# PMP9755.net
KiCad netlist of a schematic drawn in Altium Designer
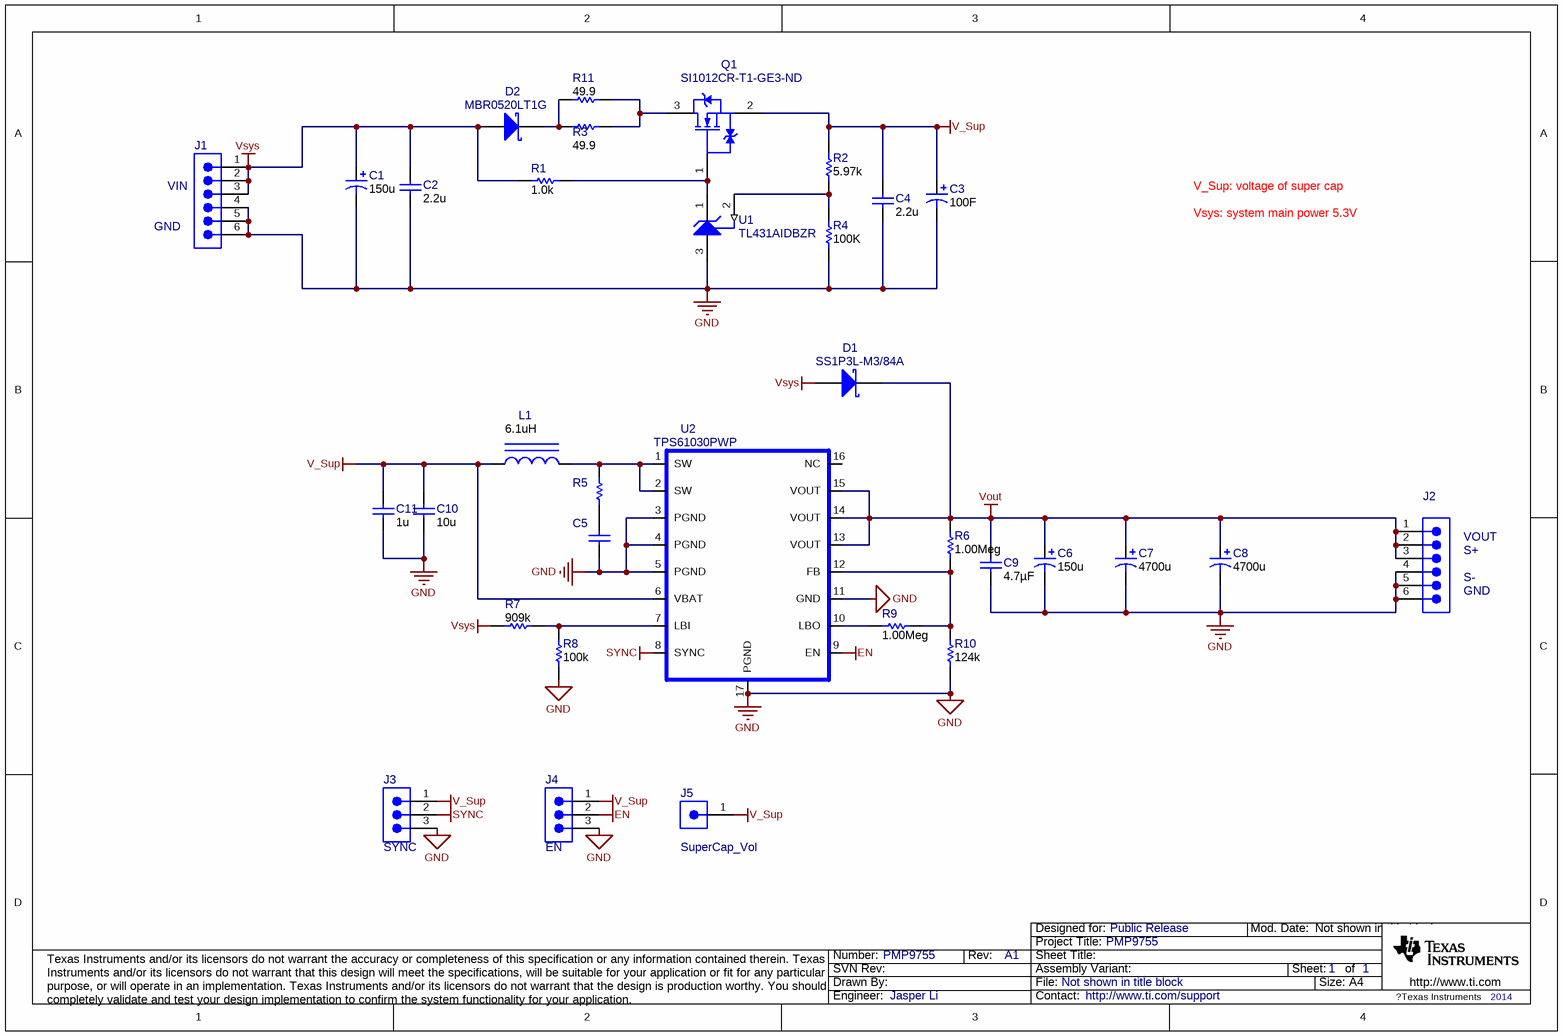
[diagram p0: PMP9755.SchDoc]

(export (version "E")
  (design (tool "Eeschema 10.0.6"))
  (components
    (comp (ref "C1")
      (value "T520B157M006ATE070")
      (footprint "3528-21")
      (description "CAP, TA, 150uF, 6.3V, +/-20%, 0.07 ohm, SMD")
      (fields
        (field (name "VALUEDISPLAYED") "150u")
        (field (name "MANUFACTURER") "Kemet")
        (field (name "PUBLISHER") "Texas Instruments")
      )
      (libsource (lib "Capacitor_Tantalum") (part "T520B157M006ATE070"))
    )
    (comp (ref "C2")
      (value "GRM188R61A225KE34D")
      (footprint "0603")
      (description "CAP, CERM, 2.2uF, 10V, +/-10%, X5R, 0603")
      (fields
        (field (name "VALUEDISPLAYED") "2.2u")
        (field (name "MANUFACTURER") "MuRata")
        (field (name "PUBLISHER") "Texas Instruments")
      )
      (libsource (lib "Capacitor_Ceramic") (part "GRM188R61A225KE34D"))
    )
    (comp (ref "C3")
      (value "HVZ0E107NF-LT")
      (footprint "HV_2500x5000")
      (description "CAP, Electric Double Layer, 100 F, 2.7 V, +30/-50%, 0.03 ohm, TH")
      (fields
        (field (name "VALUEDISPLAYED") "100F")
        (field (name "MANUFACTURER") "Kemet")
        (field (name "PUBLISHER") "Texas Instruments")
      )
      (libsource (lib "Capacitor_Other") (part "HVZ0E107NF-LT"))
    )
    (comp (ref "C4")
      (value "GRM188R60J225KE19D")
      (footprint "0603")
      (description "CAP, CERM, 2.2uF, 6.3V, +/-10%, X5R, 0603")
      (fields
        (field (name "VALUEDISPLAYED") "2.2u")
        (field (name "MANUFACTURER") "MuRata")
        (field (name "PUBLISHER") "Texas Instruments")
      )
      (libsource (lib "Capacitor_Ceramic") (part "GRM188R60J225KE19D"))
    )
    (comp (ref "C5")
      (value "GRM1885C1H101JA01D")
      (footprint "0603")
      (description "CAP, CERM, 100pF, 50V, +/-5%, C0G/NP0, 0603")
      (fields (field (name "MANUFACTURER") "MuRata") (field (name "PUBLISHER") "Texas Instruments"))
      (libsource (lib "Capacitor_Ceramic") (part "GRM1885C1H101JA01D"))
    )
    (comp (ref "C6")
      (value "T520B157M006ATE070")
      (footprint "3528-21")
      (description "CAP, TA, 150uF, 6.3V, +/-20%, 0.07 ohm, SMD")
      (fields
        (field (name "VALUEDISPLAYED") "150u")
        (field (name "MANUFACTURER") "Kemet")
        (field (name "PUBLISHER") "Texas Instruments")
      )
      (libsource (lib "Capacitor_Tantalum") (part "T520B157M006ATE070"))
    )
    (comp (ref "C7")
      (value "EEUFR0J472")
      (footprint "FR_1250x2500")
      (description "CAP, AL, 4700uF, 6.3V, +/-20%, 0.015 ohm, TH")
      (fields
        (field (name "VALUEDISPLAYED") "4700u")
        (field (name "MANUFACTURER") "Panasonic")
        (field (name "PUBLISHER") "Texas Instruments")
      )
      (libsource (lib "Capacitor_Aluminum") (part "EEUFR0J472"))
    )
    (comp (ref "C8")
      (value "EEUFR0J472")
      (footprint "FR_1250x2500")
      (description "CAP, AL, 4700uF, 6.3V, +/-20%, 0.015 ohm, TH")
      (fields
        (field (name "VALUEDISPLAYED") "4700u")
        (field (name "MANUFACTURER") "Panasonic")
        (field (name "PUBLISHER") "Texas Instruments")
      )
      (libsource (lib "Capacitor_Aluminum") (part "EEUFR0J472"))
    )
    (comp (ref "C9")
      (value "GRM188R61C475KAAJ")
      (footprint "0603")
      (description "CAP, CERM, 4.7 µF, 16 V, +/- 10%, X5R, 0603")
      (fields
        (field (name "VALUEDISPLAYED") "4.7µF")
        (field (name "MANUFACTURER") "MuRata")
        (field (name "PUBLISHER") "Texas Instruments")
      )
      (libsource (lib "Capacitor_Ceramic") (part "GRM188R61C475KAAJ"))
    )
    (comp (ref "C10")
      (value "GRM188R61A106ME69")
      (footprint "0603")
      (description "CAP, CERM, 10uF, 10V, +/-20%, X5R, 0603")
      (fields
        (field (name "VALUEDISPLAYED") "10u")
        (field (name "MANUFACTURER") "MuRata")
        (field (name "PUBLISHER") "Texas Instruments")
      )
      (libsource (lib "Capacitor_Ceramic") (part "GRM188R61A106ME69"))
    )
    (comp (ref "C11")
      (value "GRM185R60J105KE26D")
      (footprint "0603")
      (description "CAP, CERM, 1uF, 6.3V, +/-10%, X5R, 0603")
      (fields
        (field (name "VALUEDISPLAYED") "1u")
        (field (name "MANUFACTURER") "MuRata")
        (field (name "PUBLISHER") "Texas Instruments")
      )
      (libsource (lib "Capacitor_Ceramic") (part "GRM185R60J105KE26D"))
    )
    (comp (ref "D1")
      (value "SS1P3L-M3/84A")
      (footprint "DO-220AA")
      (description "Diode, Schottky, 30V, 1.5A, DO-220AA")
      (fields
        (field (name "MANUFACTURER") "Vishay-Semiconductor")
        (field (name "PUBLISHER") "Texas Instruments")
      )
      (libsource (lib "Diode") (part "SS1P3L-M3/84A"))
    )
    (comp (ref "D2")
      (value "MBR0520LT1G")
      (footprint "SOD-123")
      (description "Diode, Schottky, 20V, 0.5A, SOD-123")
      (fields (field (name "MANUFACTURER") "ON Semiconductor") (field (name "PUBLISHER") "Texas Instruments"))
      (libsource (lib "Diode") (part "MBR0520LT1G"))
    )
    (comp (ref "J1")
      (value "TSW-106-07-G-S")
      (footprint "TSW-106-07-G-S")
      (description "Header, TH, 100mil, 6x1, Gold plated, 230 mil above insulator")
      (fields
        (field (name "MANUFACTURER") "Samtec, Inc.")
        (field (name "ALTERNATE PARTNUMBER") "Equivalent")
        (field (name "PUBLISHER") "Texas Instruments")
      )
      (libsource (lib "Connectors") (part "TSW-106-07-G-S"))
    )
    (comp (ref "J2")
      (value "TSW-106-07-G-S")
      (footprint "TSW-106-07-G-S")
      (description "Header, TH, 100mil, 6x1, Gold plated, 230 mil above insulator")
      (fields
        (field (name "MANUFACTURER") "Samtec, Inc.")
        (field (name "ALTERNATE PARTNUMBER") "Equivalent")
        (field (name "PUBLISHER") "Texas Instruments")
      )
      (libsource (lib "") (part "TSW-106-07-G-S_1"))
    )
    (comp (ref "J3")
      (value "TSW-103-07-G-S")
      (footprint "TSW-103-07-G-S")
      (description "Header, TH, 100mil, 3x1, Gold plated, 230 mil above insulator")
      (fields
        (field (name "MANUFACTURER") "Samtec, Inc.")
        (field (name "ALTERNATE PARTNUMBER") "Equivalent")
        (field (name "PUBLISHER") "Texas Instruments")
      )
      (libsource (lib "Connectors") (part "TSW-103-07-G-S"))
    )
    (comp (ref "J4")
      (value "TSW-103-07-G-S")
      (footprint "TSW-103-07-G-S")
      (description "Header, TH, 100mil, 3x1, Gold plated, 230 mil above insulator")
      (fields
        (field (name "MANUFACTURER") "Samtec, Inc.")
        (field (name "ALTERNATE PARTNUMBER") "Equivalent")
        (field (name "PUBLISHER") "Texas Instruments")
      )
      (libsource (lib "Connectors") (part "TSW-103-07-G-S"))
    )
    (comp (ref "J5")
      (value "TSW-101-17-T-S")
      (footprint "Samtec_TSW-101-17-T-S")
      (description "CONN HEADER 1POS .100\" SNGL TIN, TH")
      (fields
        (field (name "MANUFACTURER") "Samtec")
        (field (name "SYMBOLCREATOR") "a0412235")
        (field (name "PUBLISHER") "Texas Instruments")
      )
      (libsource (lib "Connectors") (part "TSW-101-17-T-S"))
    )
    (comp (ref "L1")
      (value "6.1uH")
      (footprint "cdrh127")
      (description "Inductor, Shielded Drum Core, Ferrite, 6.1uH, 6.6A, 0.0176 ohm, SMD")
      (fields
        (field (name "PARTNUMBER") "CDRH127NP-6R1NC")
        (field (name "MANUFACTURER") "Sumida")
        (field (name "PUBLISHER") "Texas Instruments")
      )
      (libsource (lib "Inductor_Sumida") (part "CDRH127NP-6R1NC"))
    )
    (comp (ref "Q1")
      (value "SI1012CR-T1-GE3-ND")
      (footprint "SOT-416")
      (description "MOSFET, N/P-CH, 20V, 0.63A, SOT-416")
      (fields
        (field (name "MANUFACTURER") "Vishay-Siliconix")
        (field (name "SYMBOLCREATOR") "a0411947")
        (field (name "PUBLISHER") "Texas Instruments")
      )
      (libsource (lib "FETs") (part "SI1012CR-T1-GE3-ND"))
    )
    (comp (ref "R1")
      (value "1.0k")
      (footprint "0603")
      (description "RES, 1.0k ohm, 5%, 0.1W, 0603")
      (fields
        (field (name "PARTNUMBER") "CRCW06031K00JNEA")
        (field (name "MANUFACTURER") "Vishay-Dale")
        (field (name "PUBLISHER") "Texas Instruments")
      )
      (libsource (lib "Resistor_0603") (part "CRCW06031K00JNEA"))
    )
    (comp (ref "R2")
      (value "5.97k")
      (footprint "0603")
      (description "RES, 5.97k ohm, 0.1%, 0.1W, 0603")
      (fields
        (field (name "PARTNUMBER") "RT0603BRD075K97L")
        (field (name "MANUFACTURER") "Yageo America")
        (field (name "PUBLISHER") "Texas Instruments")
      )
      (libsource (lib "Resistor_0603") (part "RT0603BRD075K97L"))
    )
    (comp (ref "R3")
      (value "49.9")
      (footprint "2512")
      (description "RES, 49.9 ohm, 1%, 1W, 2512")
      (fields
        (field (name "PARTNUMBER") "CRCW251249R9FKEG")
        (field (name "MANUFACTURER") "Vishay-Dale")
        (field (name "PUBLISHER") "Texas Instruments")
      )
      (libsource (lib "Resistor_2512") (part "CRCW251249R9FKEG"))
    )
    (comp (ref "R4")
      (value "100K")
      (footprint "0603")
      (description "RES, 100k ohm, 0.5%, 0.1W, 0603")
      (fields
        (field (name "PARTNUMBER") "RT0603DRE07100KL")
        (field (name "MANUFACTURER") "Yageo America")
        (field (name "PUBLISHER") "Texas Instruments")
      )
      (libsource (lib "Resistor_0603") (part "RT0603DRE07100KL"))
    )
    (comp (ref "R5")
      (value "CRCW0603100RJNEA")
      (footprint "0603")
      (description "RES, 100 ohm, 5%, 0.1W, 0603")
      (fields (field (name "MANUFACTURER") "Vishay-Dale") (field (name "PUBLISHER") "Texas Instruments"))
      (libsource (lib "Resistor_0603") (part "CRCW0603100RJNEA"))
    )
    (comp (ref "R6")
      (value "1.00Meg")
      (footprint "0603")
      (description "RES, 1.00Meg ohm, 1%, 0.1W, 0603")
      (fields
        (field (name "PARTNUMBER") "RC0603FR-071ML")
        (field (name "MANUFACTURER") "Yageo America")
        (field (name "PUBLISHER") "Texas Instruments")
      )
      (libsource (lib "Resistor_0603") (part "RC0603FR-071ML"))
    )
    (comp (ref "R7")
      (value "909k")
      (footprint "0603")
      (description "RES, 909k ohm, 1%, 0.1W, 0603")
      (fields
        (field (name "PARTNUMBER") "RC0603FR-07909KL")
        (field (name "MANUFACTURER") "Yageo America")
        (field (name "PUBLISHER") "Texas Instruments")
      )
      (libsource (lib "Resistor_0603") (part "RC0603FR-07909KL"))
    )
    (comp (ref "R8")
      (value "100k")
      (footprint "0603")
      (description "RES, 100k ohm, 0.5%, 0.1W, 0603")
      (fields
        (field (name "PARTNUMBER") "RT0603DRE07100KL")
        (field (name "MANUFACTURER") "Yageo America")
        (field (name "PUBLISHER") "Texas Instruments")
      )
      (libsource (lib "Resistor_0603") (part "RT0603DRE07100KL"))
    )
    (comp (ref "R9")
      (value "1.00Meg")
      (footprint "0603")
      (description "RES, 1.00Meg ohm, 1%, 0.1W, 0603")
      (fields
        (field (name "PARTNUMBER") "RC0603FR-071ML")
        (field (name "MANUFACTURER") "Yageo America")
        (field (name "PUBLISHER") "Texas Instruments")
      )
      (libsource (lib "Resistor_0603") (part "RC0603FR-071ML"))
    )
    (comp (ref "R10")
      (value "124k")
      (footprint "0603")
      (description "RES, 124k ohm, 1%, 0.1W, 0603")
      (fields
        (field (name "PARTNUMBER") "CRCW0603124KFKEA")
        (field (name "MANUFACTURER") "Vishay-Dale")
        (field (name "PUBLISHER") "Texas Instruments")
      )
      (libsource (lib "Resistor_0603") (part "CRCW0603124KFKEA"))
    )
    (comp (ref "R11")
      (value "49.9")
      (footprint "2512")
      (description "RES, 49.9 ohm, 1%, 1W, 2512")
      (fields
        (field (name "PARTNUMBER") "CRCW251249R9FKEG")
        (field (name "MANUFACTURER") "Vishay-Dale")
        (field (name "PUBLISHER") "Texas Instruments")
      )
      (libsource (lib "Resistor_2512") (part "CRCW251249R9FKEG"))
    )
    (comp (ref "U1")
      (value "TL431AIDBZR")
      (footprint "DBZ0003A_N")
      (fields
        (field (name "MANUFACTURER") "Texas Instruments")
        (field (name "ALTERNATE PARTNUMBER") "Equivalent")
      )
      (libsource (lib "TI Power Management Shunt Voltage Reference") (part "TL431AIDBZR"))
    )
    (comp (ref "U2")
      (value "TPS61030PWP")
      (footprint "PWP16")
      (description "IC, Li ION, Boost converter, Adj V.")
      (fields (field (name "MANUFACTURER") "Texas Instruments"))
      (libsource (lib "PADSlegacy_PMP") (part "TPS61030PWP"))
    )
  )
  (nets
    (net (code "1") (name "EN") (class "Default")
      (node (ref "J4") (pin "2") (pinfunction "2_2") (pintype "passive"))
      (node (ref "U2") (pin "9") (pinfunction "EN_9") (pintype "passive"))
    )
    (net (code "2") (name "GND") (class "Default")
      (node (ref "C1") (pin "2") (pinfunction "-_2") (pintype "passive"))
      (node (ref "C10") (pin "2") (pinfunction "2_2") (pintype "passive"))
      (node (ref "C11") (pin "2") (pinfunction "2_2") (pintype "passive"))
      (node (ref "C2") (pin "2") (pinfunction "2_2") (pintype "passive"))
      (node (ref "C3") (pin "2") (pinfunction "-_2") (pintype "passive"))
      (node (ref "C4") (pin "2") (pinfunction "2_2") (pintype "passive"))
      (node (ref "C5") (pin "2") (pinfunction "2_2") (pintype "passive"))
      (node (ref "C6") (pin "2") (pinfunction "-_2") (pintype "passive"))
      (node (ref "C7") (pin "2") (pinfunction "-_2") (pintype "passive"))
      (node (ref "C8") (pin "2") (pinfunction "-_2") (pintype "passive"))
      (node (ref "C9") (pin "2") (pinfunction "2_2") (pintype "passive"))
      (node (ref "J1") (pin "4") (pinfunction "4_4") (pintype "passive"))
      (node (ref "J1") (pin "5") (pinfunction "5_5") (pintype "passive"))
      (node (ref "J1") (pin "6") (pinfunction "6_6") (pintype "passive"))
      (node (ref "J2") (pin "4") (pinfunction "4_4") (pintype "passive"))
      (node (ref "J2") (pin "5") (pinfunction "5_5") (pintype "passive"))
      (node (ref "J2") (pin "6") (pinfunction "6_6") (pintype "passive"))
      (node (ref "J3") (pin "3") (pinfunction "3_3") (pintype "passive"))
      (node (ref "J4") (pin "3") (pinfunction "3_3") (pintype "passive"))
      (node (ref "R10") (pin "1") (pinfunction "1_1") (pintype "passive"))
      (node (ref "R4") (pin "2") (pinfunction "2_2") (pintype "passive"))
      (node (ref "R8") (pin "1") (pinfunction "1_1") (pintype "passive"))
      (node (ref "U1") (pin "3") (pinfunction "ANODE_3") (pintype "passive"))
      (node (ref "U2") (pin "11") (pinfunction "GND_11") (pintype "passive"))
      (node (ref "U2") (pin "17") (pinfunction "PGND_17") (pintype "passive"))
      (node (ref "U2") (pin "3") (pinfunction "PGND_3") (pintype "passive"))
      (node (ref "U2") (pin "4") (pinfunction "PGND_4") (pintype "passive"))
      (node (ref "U2") (pin "5") (pinfunction "PGND_5") (pintype "passive"))
    )
    (net (code "3") (name "Net-(C5-Pad1)") (class "Default")
      (node (ref "C5") (pin "1") (pinfunction "1_1") (pintype "passive"))
      (node (ref "R5") (pin "1") (pinfunction "1_1") (pintype "passive"))
    )
    (net (code "4") (name "Net-(D2-K)") (class "Default")
      (node (ref "D2") (pin "1") (pinfunction "K_1") (pintype "passive"))
      (node (ref "R11") (pin "1") (pinfunction "1_1") (pintype "passive"))
      (node (ref "R3") (pin "1") (pinfunction "1_1") (pintype "passive"))
    )
    (net (code "5") (name "Net-(L1-Pad2)") (class "Default")
      (node (ref "L1") (pin "2") (pinfunction "2_2") (pintype "passive"))
      (node (ref "R5") (pin "2") (pinfunction "2_2") (pintype "passive"))
      (node (ref "U2") (pin "1") (pinfunction "SW_1") (pintype "passive"))
      (node (ref "U2") (pin "2") (pinfunction "SW_2") (pintype "passive"))
    )
    (net (code "6") (name "Net-(Q1-D)") (class "Default")
      (node (ref "Q1") (pin "3") (pinfunction "D_3") (pintype "passive"))
      (node (ref "R11") (pin "2") (pinfunction "2_2") (pintype "passive"))
      (node (ref "R3") (pin "2") (pinfunction "2_2") (pintype "passive"))
    )
    (net (code "7") (name "Net-(Q1-G)") (class "Default")
      (node (ref "Q1") (pin "1") (pinfunction "G_1") (pintype "passive"))
      (node (ref "R1") (pin "2") (pinfunction "2_2") (pintype "passive"))
      (node (ref "U1") (pin "1") (pinfunction "CATHODE_1") (pintype "passive"))
    )
    (net (code "8") (name "Net-(U1-REF)") (class "Default")
      (node (ref "R2") (pin "1") (pinfunction "1_1") (pintype "passive"))
      (node (ref "R4") (pin "1") (pinfunction "1_1") (pintype "passive"))
      (node (ref "U1") (pin "2") (pinfunction "REF_2") (pintype "input"))
    )
    (net (code "9") (name "Net-(U2-FB)") (class "Default")
      (node (ref "R10") (pin "2") (pinfunction "2_2") (pintype "passive"))
      (node (ref "R6") (pin "1") (pinfunction "1_1") (pintype "passive"))
      (node (ref "R9") (pin "1") (pinfunction "1_1") (pintype "passive"))
      (node (ref "U2") (pin "12") (pinfunction "FB_12") (pintype "passive"))
    )
    (net (code "10") (name "Net-(U2-LBI)") (class "Default")
      (node (ref "R7") (pin "2") (pinfunction "2_2") (pintype "passive"))
      (node (ref "R8") (pin "2") (pinfunction "2_2") (pintype "passive"))
      (node (ref "U2") (pin "7") (pinfunction "LBI_7") (pintype "passive"))
    )
    (net (code "11") (name "Net-(U2-LBO)") (class "Default")
      (node (ref "R9") (pin "2") (pinfunction "2_2") (pintype "passive"))
      (node (ref "U2") (pin "10") (pinfunction "LBO_10") (pintype "passive"))
    )
    (net (code "12") (name "SYNC") (class "Default")
      (node (ref "J3") (pin "2") (pinfunction "2_2") (pintype "passive"))
      (node (ref "U2") (pin "8") (pinfunction "SYNC_8") (pintype "passive"))
    )
    (net (code "13") (name "V_Sup") (class "Default")
      (node (ref "C10") (pin "1") (pinfunction "1_1") (pintype "passive"))
      (node (ref "C11") (pin "1") (pinfunction "1_1") (pintype "passive"))
      (node (ref "C3") (pin "1") (pinfunction "+_1") (pintype "passive"))
      (node (ref "C4") (pin "1") (pinfunction "1_1") (pintype "passive"))
      (node (ref "J3") (pin "1") (pinfunction "1_1") (pintype "passive"))
      (node (ref "J4") (pin "1") (pinfunction "1_1") (pintype "passive"))
      (node (ref "J5") (pin "1") (pinfunction "1_1") (pintype "passive"))
      (node (ref "L1") (pin "1") (pinfunction "1_1") (pintype "passive"))
      (node (ref "Q1") (pin "2") (pinfunction "S_2") (pintype "passive"))
      (node (ref "R2") (pin "2") (pinfunction "2_2") (pintype "passive"))
      (node (ref "U2") (pin "6") (pinfunction "VBAT_6") (pintype "passive"))
    )
    (net (code "14") (name "Vout") (class "Default")
      (node (ref "C6") (pin "1") (pinfunction "+_1") (pintype "passive"))
      (node (ref "C7") (pin "1") (pinfunction "+_1") (pintype "passive"))
      (node (ref "C8") (pin "1") (pinfunction "+_1") (pintype "passive"))
      (node (ref "C9") (pin "1") (pinfunction "1_1") (pintype "passive"))
      (node (ref "D1") (pin "1") (pinfunction "K_1") (pintype "passive"))
      (node (ref "J2") (pin "1") (pinfunction "1_1") (pintype "passive"))
      (node (ref "J2") (pin "2") (pinfunction "2_2") (pintype "passive"))
      (node (ref "J2") (pin "3") (pinfunction "3_3") (pintype "passive"))
      (node (ref "R6") (pin "2") (pinfunction "2_2") (pintype "passive"))
      (node (ref "U2") (pin "13") (pinfunction "VOUT_13") (pintype "passive"))
      (node (ref "U2") (pin "14") (pinfunction "VOUT_14") (pintype "passive"))
      (node (ref "U2") (pin "15") (pinfunction "VOUT_15") (pintype "passive"))
    )
    (net (code "15") (name "Vsys") (class "Default")
      (node (ref "C1") (pin "1") (pinfunction "+_1") (pintype "passive"))
      (node (ref "C2") (pin "1") (pinfunction "1_1") (pintype "passive"))
      (node (ref "D1") (pin "2") (pinfunction "A_2") (pintype "passive"))
      (node (ref "D2") (pin "2") (pinfunction "A_2") (pintype "passive"))
      (node (ref "J1") (pin "1") (pinfunction "1_1") (pintype "passive"))
      (node (ref "J1") (pin "2") (pinfunction "2_2") (pintype "passive"))
      (node (ref "J1") (pin "3") (pinfunction "3_3") (pintype "passive"))
      (node (ref "R1") (pin "1") (pinfunction "1_1") (pintype "passive"))
      (node (ref "R7") (pin "1") (pinfunction "1_1") (pintype "passive"))
    )
    (net (code "16") (name "unconnected-(U2-NC-Pad16)") (class "Default")
      (node (ref "U2") (pin "16") (pinfunction "NC_16") (pintype "passive"))
    )
  )
)
